# FPGA.net
KiCad netlist of a schematic drawn in Altium Designer
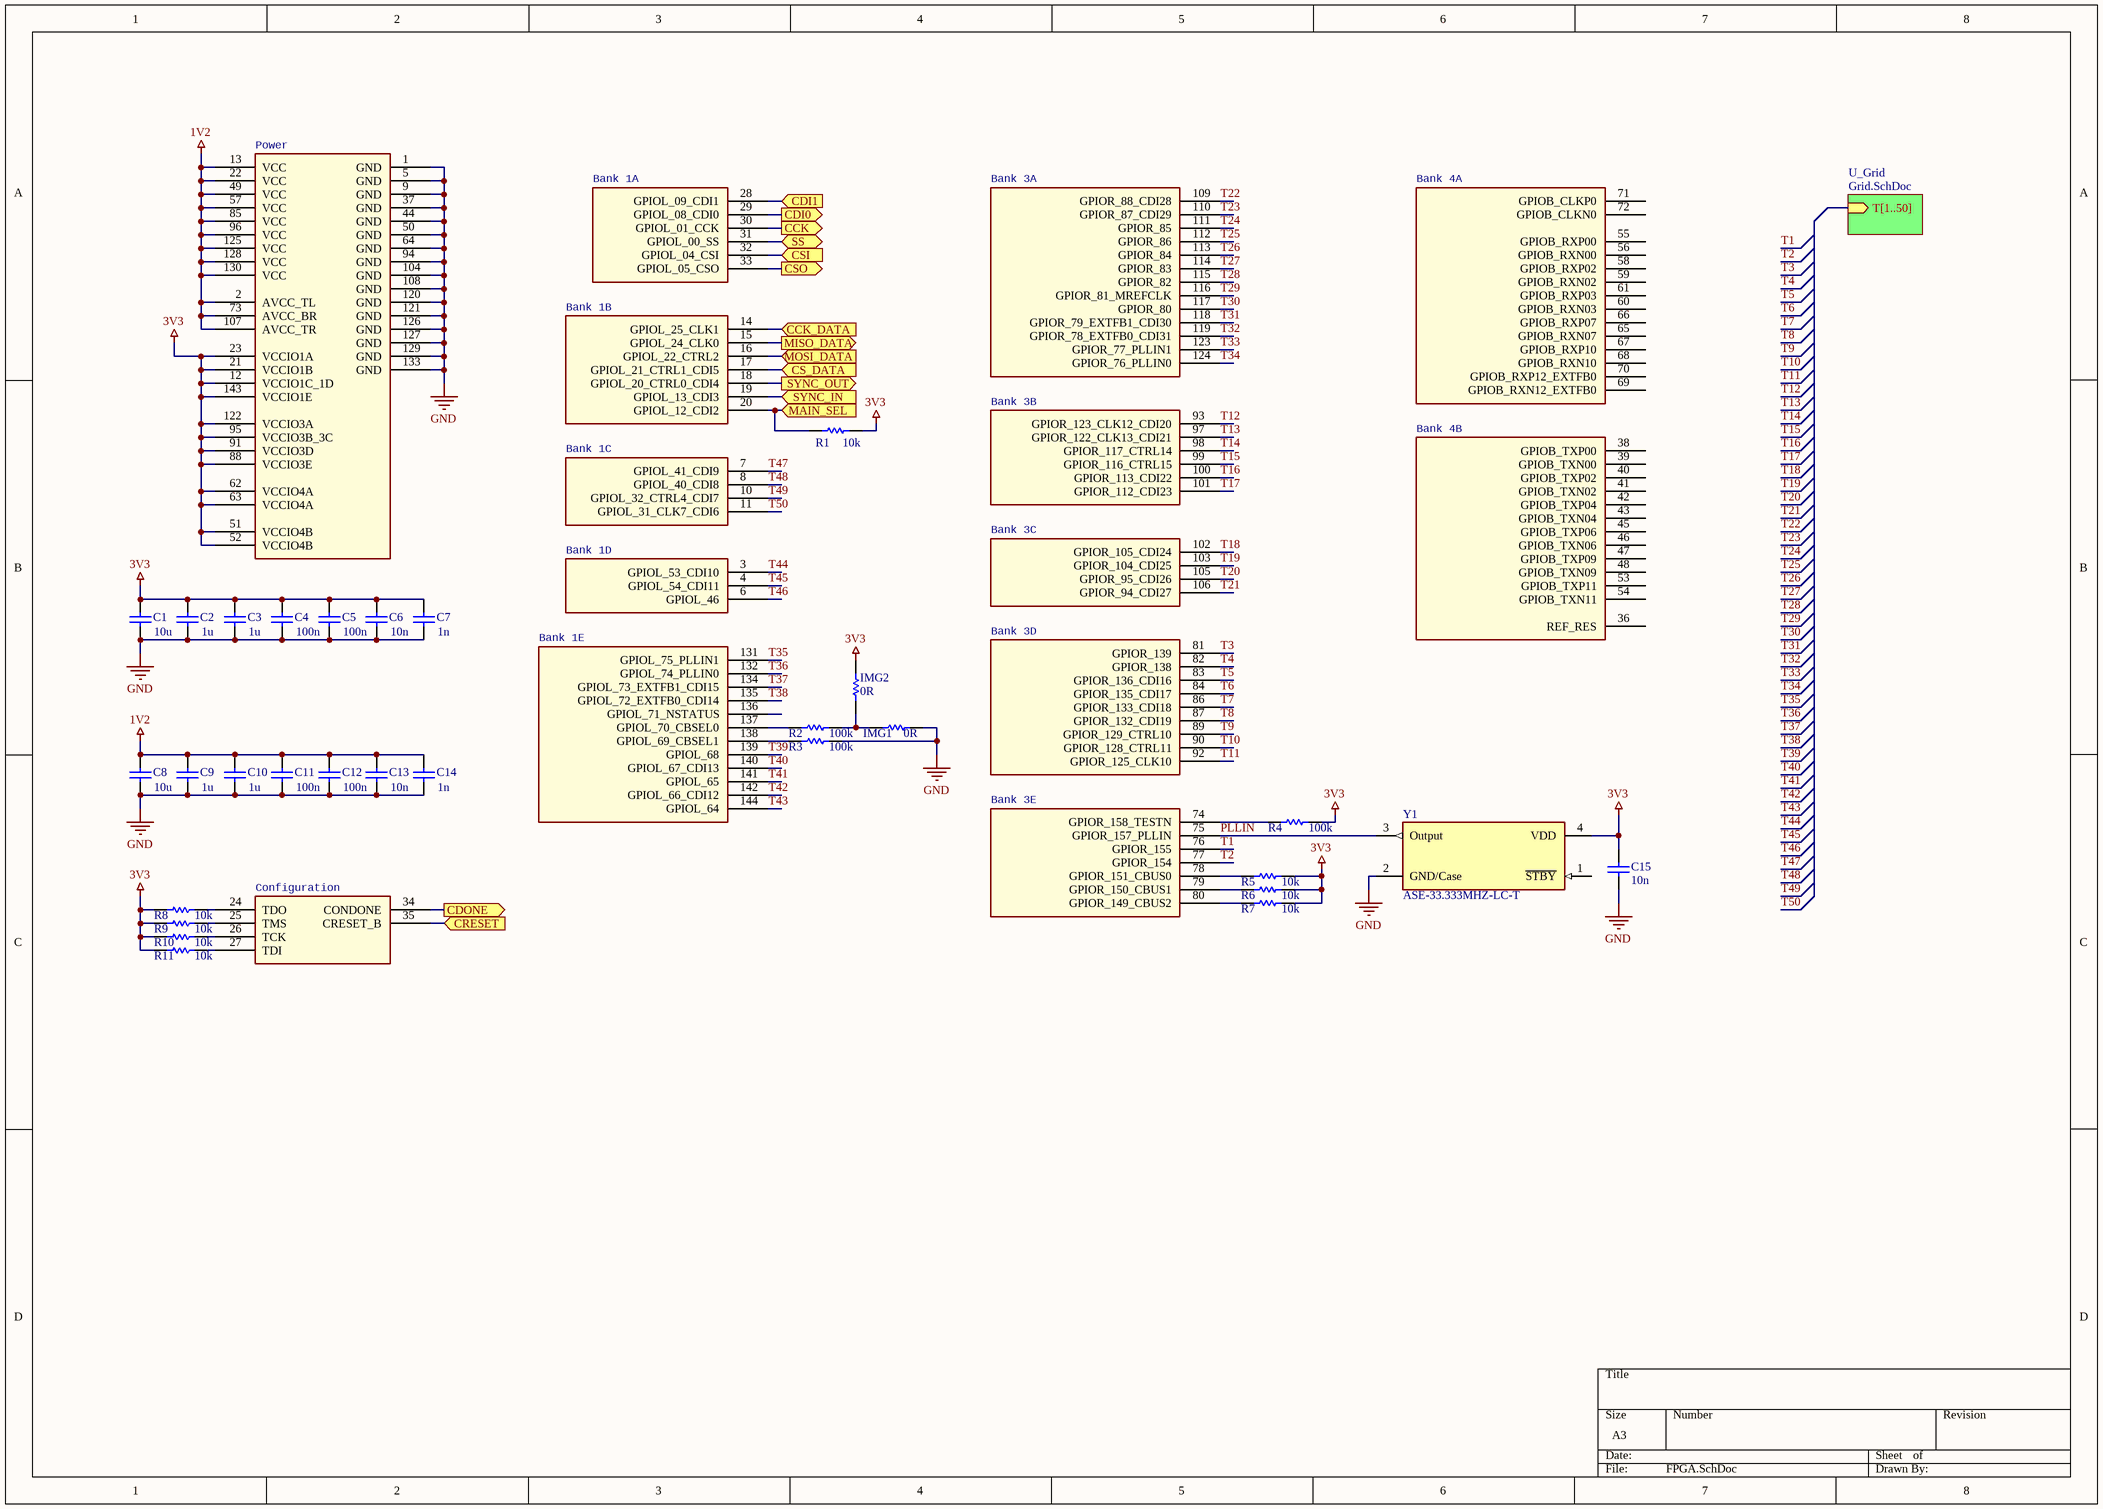
[diagram p0: FPGA.SchDoc]

(export (version "E")
  (design (tool "Eeschema 10.0.6"))
  (components
    (comp (ref "C1")
      (value "10u")
      (footprint "SAMS-C0603-2_M")
      (description "Multi-layer Ceramic Capacitor, -55 to 125 degC, 2-Pin SMD (0603), RoHS, Tape and Reel")
      (fields (field (name "MANUFACTURER") "Samsung Electro-Mechanics"))
      (libsource (lib "Altium Content Vault") (part "CAP-NP-2"))
    )
    (comp (ref "C2")
      (value "1u")
      (footprint "SAMS-C0603-2_M")
      (description "Multi-layer Ceramic Capacitor, -55 to 125 degC, 2-Pin SMD (0603), RoHS, Tape and Reel")
      (fields (field (name "MANUFACTURER") "Samsung Electro-Mechanics"))
      (libsource (lib "Altium Content Vault") (part "CAP-NP-2"))
    )
    (comp (ref "C3")
      (value "1u")
      (footprint "SAMS-C0603-2_M")
      (description "Multi-layer Ceramic Capacitor, -55 to 125 degC, 2-Pin SMD (0603), RoHS, Tape and Reel")
      (fields (field (name "MANUFACTURER") "Samsung Electro-Mechanics"))
      (libsource (lib "Altium Content Vault") (part "CAP-NP-2"))
    )
    (comp (ref "C4")
      (value "100n")
      (footprint "SAMS-C0603-2_M")
      (description "Multi-layer Ceramic Capacitor, -55 to 125 degC, 2-Pin SMD (0603), RoHS, Tape and Reel")
      (fields (field (name "MANUFACTURER") "Samsung Electro-Mechanics"))
      (libsource (lib "Altium Content Vault") (part "CAP-NP-2"))
    )
    (comp (ref "C5")
      (value "100n")
      (footprint "SAMS-C0603-2_M")
      (description "Multi-layer Ceramic Capacitor, -55 to 125 degC, 2-Pin SMD (0603), RoHS, Tape and Reel")
      (fields (field (name "MANUFACTURER") "Samsung Electro-Mechanics"))
      (libsource (lib "Altium Content Vault") (part "CAP-NP-2"))
    )
    (comp (ref "C6")
      (value "10n")
      (footprint "SAMS-C0603-2_M")
      (description "Multi-layer Ceramic Capacitor, -55 to 125 degC, 2-Pin SMD (0603), RoHS, Tape and Reel")
      (fields (field (name "MANUFACTURER") "Samsung Electro-Mechanics"))
      (libsource (lib "Altium Content Vault") (part "CAP-NP-2"))
    )
    (comp (ref "C7")
      (value "1n")
      (footprint "SAMS-C0603-2_M")
      (description "Multi-layer Ceramic Capacitor, -55 to 125 degC, 2-Pin SMD (0603), RoHS, Tape and Reel")
      (fields (field (name "MANUFACTURER") "Samsung Electro-Mechanics"))
      (libsource (lib "Altium Content Vault") (part "CAP-NP-2"))
    )
    (comp (ref "C8")
      (value "10u")
      (footprint "SAMS-C0603-2_M")
      (description "Multi-layer Ceramic Capacitor, -55 to 125 degC, 2-Pin SMD (0603), RoHS, Tape and Reel")
      (fields (field (name "MANUFACTURER") "Samsung Electro-Mechanics"))
      (libsource (lib "Altium Content Vault") (part "CAP-NP-2"))
    )
    (comp (ref "C9")
      (value "1u")
      (footprint "SAMS-C0603-2_M")
      (description "Multi-layer Ceramic Capacitor, -55 to 125 degC, 2-Pin SMD (0603), RoHS, Tape and Reel")
      (fields (field (name "MANUFACTURER") "Samsung Electro-Mechanics"))
      (libsource (lib "Altium Content Vault") (part "CAP-NP-2"))
    )
    (comp (ref "C10")
      (value "1u")
      (footprint "SAMS-C0603-2_M")
      (description "Multi-layer Ceramic Capacitor, -55 to 125 degC, 2-Pin SMD (0603), RoHS, Tape and Reel")
      (fields (field (name "MANUFACTURER") "Samsung Electro-Mechanics"))
      (libsource (lib "Altium Content Vault") (part "CAP-NP-2"))
    )
    (comp (ref "C11")
      (value "100n")
      (footprint "SAMS-C0603-2_M")
      (description "Multi-layer Ceramic Capacitor, -55 to 125 degC, 2-Pin SMD (0603), RoHS, Tape and Reel")
      (fields (field (name "MANUFACTURER") "Samsung Electro-Mechanics"))
      (libsource (lib "Altium Content Vault") (part "CAP-NP-2"))
    )
    (comp (ref "C12")
      (value "100n")
      (footprint "SAMS-C0603-2_M")
      (description "Multi-layer Ceramic Capacitor, -55 to 125 degC, 2-Pin SMD (0603), RoHS, Tape and Reel")
      (fields (field (name "MANUFACTURER") "Samsung Electro-Mechanics"))
      (libsource (lib "Altium Content Vault") (part "CAP-NP-2"))
    )
    (comp (ref "C13")
      (value "10n")
      (footprint "SAMS-C0603-2_M")
      (description "Multi-layer Ceramic Capacitor, -55 to 125 degC, 2-Pin SMD (0603), RoHS, Tape and Reel")
      (fields (field (name "MANUFACTURER") "Samsung Electro-Mechanics"))
      (libsource (lib "Altium Content Vault") (part "CAP-NP-2"))
    )
    (comp (ref "C14")
      (value "1n")
      (footprint "SAMS-C0603-2_M")
      (description "Multi-layer Ceramic Capacitor, -55 to 125 degC, 2-Pin SMD (0603), RoHS, Tape and Reel")
      (fields (field (name "MANUFACTURER") "Samsung Electro-Mechanics"))
      (libsource (lib "Altium Content Vault") (part "CAP-NP-2"))
    )
    (comp (ref "C15")
      (value "10n")
      (footprint "SAMS-C0603-2_M")
      (description "Multi-layer Ceramic Capacitor, -55 to 125 degC, 2-Pin SMD (0603), RoHS, Tape and Reel")
      (fields (field (name "MANUFACTURER") "Samsung Electro-Mechanics"))
      (libsource (lib "Altium Content Vault") (part "CAP-NP-2"))
    )
    (comp (ref "IMG1")
      (value "0R")
      (footprint "RESC1005X40X20NL05T10")
      (fields
        (field (name "MANUFACTURER") "Vishay BCcomponents")
        (field (name "PART NUMBER") "TNPW040210K0DEED")
      )
      (libsource (lib "Altium Content Vault") (part "RES"))
    )
    (comp (ref "IMG2")
      (value "0R")
      (footprint "RESC1005X40X20NL05T10")
      (fields
        (field (name "MANUFACTURER") "Vishay BCcomponents")
        (field (name "PART NUMBER") "TNPW040210K0DEED")
      )
      (libsource (lib "Altium Content Vault") (part "RES"))
    )
    (comp (ref "R1")
      (value "10k")
      (footprint "RESC1609X55X30LL15T15")
      (description "Chip Resistor, 10 KOhm, +/- 1%, 0.1 W, -55 to 155 degC, 0603 (1608 Metric), RoHS, Tape and Reel")
      (fields (field (name "TOLERANCE") "1%") (field (name "MANUFACTURER") "Panasonic"))
      (libsource (lib "Altium Content Vault") (part "RES-2"))
    )
    (comp (ref "R2")
      (value "100k")
      (footprint "RESC1609X55X30LL15T15")
      (description "Chip Resistor, 10 KOhm, +/- 1%, 0.1 W, -55 to 155 degC, 0603 (1608 Metric), RoHS, Tape and Reel")
      (fields (field (name "TOLERANCE") "1%") (field (name "MANUFACTURER") "Panasonic"))
      (libsource (lib "Altium Content Vault") (part "RES-2"))
    )
    (comp (ref "R3")
      (value "100k")
      (footprint "RESC1609X55X30LL15T15")
      (description "Chip Resistor, 10 KOhm, +/- 1%, 0.1 W, -55 to 155 degC, 0603 (1608 Metric), RoHS, Tape and Reel")
      (fields (field (name "TOLERANCE") "1%") (field (name "MANUFACTURER") "Panasonic"))
      (libsource (lib "Altium Content Vault") (part "RES-2"))
    )
    (comp (ref "R4")
      (value "100k")
      (footprint "RESC1609X55X30LL15T15")
      (description "Chip Resistor, 10 KOhm, +/- 1%, 0.1 W, -55 to 155 degC, 0603 (1608 Metric), RoHS, Tape and Reel")
      (fields (field (name "TOLERANCE") "1%") (field (name "MANUFACTURER") "Panasonic"))
      (libsource (lib "Altium Content Vault") (part "RES-2"))
    )
    (comp (ref "R5")
      (value "10k")
      (footprint "RESC1609X55X30LL15T15")
      (description "Chip Resistor, 10 KOhm, +/- 1%, 0.1 W, -55 to 155 degC, 0603 (1608 Metric), RoHS, Tape and Reel")
      (fields (field (name "TOLERANCE") "1%") (field (name "MANUFACTURER") "Panasonic"))
      (libsource (lib "Altium Content Vault") (part "RES-2"))
    )
    (comp (ref "R6")
      (value "10k")
      (footprint "RESC1609X55X30LL15T15")
      (description "Chip Resistor, 10 KOhm, +/- 1%, 0.1 W, -55 to 155 degC, 0603 (1608 Metric), RoHS, Tape and Reel")
      (fields (field (name "TOLERANCE") "1%") (field (name "MANUFACTURER") "Panasonic"))
      (libsource (lib "Altium Content Vault") (part "RES-2"))
    )
    (comp (ref "R7")
      (value "10k")
      (footprint "RESC1609X55X30LL15T15")
      (description "Chip Resistor, 10 KOhm, +/- 1%, 0.1 W, -55 to 155 degC, 0603 (1608 Metric), RoHS, Tape and Reel")
      (fields (field (name "TOLERANCE") "1%") (field (name "MANUFACTURER") "Panasonic"))
      (libsource (lib "Altium Content Vault") (part "RES-2"))
    )
    (comp (ref "R8")
      (value "10k")
      (footprint "RESC1609X55X30LL15T15")
      (description "Chip Resistor, 10 KOhm, +/- 1%, 0.1 W, -55 to 155 degC, 0603 (1608 Metric), RoHS, Tape and Reel")
      (fields (field (name "TOLERANCE") "1%") (field (name "MANUFACTURER") "Panasonic"))
      (libsource (lib "Altium Content Vault") (part "RES-2"))
    )
    (comp (ref "R9")
      (value "10k")
      (footprint "RESC1609X55X30LL15T15")
      (description "Chip Resistor, 10 KOhm, +/- 1%, 0.1 W, -55 to 155 degC, 0603 (1608 Metric), RoHS, Tape and Reel")
      (fields (field (name "TOLERANCE") "1%") (field (name "MANUFACTURER") "Panasonic"))
      (libsource (lib "Altium Content Vault") (part "RES-2"))
    )
    (comp (ref "R10")
      (value "10k")
      (footprint "RESC1609X55X30LL15T15")
      (description "Chip Resistor, 10 KOhm, +/- 1%, 0.1 W, -55 to 155 degC, 0603 (1608 Metric), RoHS, Tape and Reel")
      (fields (field (name "TOLERANCE") "1%") (field (name "MANUFACTURER") "Panasonic"))
      (libsource (lib "Altium Content Vault") (part "RES-2"))
    )
    (comp (ref "R11")
      (value "10k")
      (footprint "RESC1609X55X30LL15T15")
      (description "Chip Resistor, 10 KOhm, +/- 1%, 0.1 W, -55 to 155 degC, 0603 (1608 Metric), RoHS, Tape and Reel")
      (fields (field (name "TOLERANCE") "1%") (field (name "MANUFACTURER") "Panasonic"))
      (libsource (lib "Altium Content Vault") (part "RES-2"))
    )
    (comp (ref "U1")
      (value "T8Q144Cx")
      (footprint "LQFP144")
      (libsource (lib "Orcad Libraries") (part "T8Q144Cx"))
    )
    (comp (ref "Y1")
      (value "ASE-33.333MHZ-LC-T")
      (footprint "FP-ASE-MFG")
      (description "XTAL Oscillator 33.333MHz ±50ppm CMOS 3.3V 4-SMD 3.2mm x 2.5mm")
      (libsource (lib "Altium Content Vault") (part "61a724e6190563596ac712fef61ad37"))
    )
  )
  (nets
    (net (code "1") (name "/CCK") (class "Default")
      (node (ref "U1") (pin "30") (pinfunction "GPIOL_01_CCK_30") (pintype "passive"))
    )
    (net (code "2") (name "/CCK_DATA") (class "Default")
      (node (ref "U1") (pin "14") (pinfunction "GPIOL_25_CLK1_14") (pintype "passive"))
    )
    (net (code "3") (name "/CDI0") (class "Default")
      (node (ref "U1") (pin "29") (pinfunction "GPIOL_08_CDI0_29") (pintype "passive"))
    )
    (net (code "4") (name "/CDI1") (class "Default")
      (node (ref "U1") (pin "28") (pinfunction "GPIOL_09_CDI1_28") (pintype "passive"))
    )
    (net (code "5") (name "/CDONE") (class "Default")
      (node (ref "U1") (pin "34") (pinfunction "CONDONE_34") (pintype "passive"))
    )
    (net (code "6") (name "/CRESET") (class "Default")
      (node (ref "U1") (pin "35") (pinfunction "CRESET_B_35") (pintype "passive"))
    )
    (net (code "7") (name "/CSI") (class "Default")
      (node (ref "U1") (pin "32") (pinfunction "GPIOL_04_CSI_32") (pintype "passive"))
    )
    (net (code "8") (name "/CSO") (class "Default")
      (node (ref "U1") (pin "33") (pinfunction "GPIOL_05_CSO_33") (pintype "passive"))
    )
    (net (code "9") (name "/CS_DATA") (class "Default")
      (node (ref "U1") (pin "17") (pinfunction "GPIOL_21_CTRL1_CDI5_17") (pintype "passive"))
    )
    (net (code "10") (name "/MAIN_SEL") (class "Default")
      (node (ref "R1") (pin "2") (pinfunction "2_2") (pintype "passive"))
      (node (ref "U1") (pin "20") (pinfunction "GPIOL_12_CDI2_20") (pintype "passive"))
    )
    (net (code "11") (name "/MISO_DATA") (class "Default")
      (node (ref "U1") (pin "15") (pinfunction "GPIOL_24_CLK0_15") (pintype "passive"))
    )
    (net (code "12") (name "/MOSI_DATA") (class "Default")
      (node (ref "U1") (pin "16") (pinfunction "GPIOL_22_CTRL2_16") (pintype "passive"))
    )
    (net (code "13") (name "/PLLIN") (class "Default")
      (node (ref "U1") (pin "75") (pinfunction "GPIOR_157_PLLIN_75") (pintype "passive"))
      (node (ref "Y1") (pin "3") (pinfunction "Output_3") (pintype "output"))
    )
    (net (code "14") (name "/SS") (class "Default")
      (node (ref "U1") (pin "31") (pinfunction "GPIOL_00_SS_31") (pintype "passive"))
    )
    (net (code "15") (name "/SYNC_IN") (class "Default")
      (node (ref "U1") (pin "19") (pinfunction "GPIOL_13_CDI3_19") (pintype "passive"))
    )
    (net (code "16") (name "/SYNC_OUT") (class "Default")
      (node (ref "U1") (pin "18") (pinfunction "GPIOL_20_CTRL0_CDI4_18") (pintype "passive"))
    )
    (net (code "17") (name "/T1") (class "Default")
      (node (ref "U1") (pin "76") (pinfunction "GPIOR_155_76") (pintype "passive"))
    )
    (net (code "18") (name "/T2") (class "Default")
      (node (ref "U1") (pin "77") (pinfunction "GPIOR_154_77") (pintype "passive"))
    )
    (net (code "19") (name "/T3") (class "Default")
      (node (ref "U1") (pin "81") (pinfunction "GPIOR_139_81") (pintype "passive"))
    )
    (net (code "20") (name "/T4") (class "Default")
      (node (ref "U1") (pin "82") (pinfunction "GPIOR_138_82") (pintype "passive"))
    )
    (net (code "21") (name "/T5") (class "Default")
      (node (ref "U1") (pin "83") (pinfunction "GPIOR_136_CDI16_83") (pintype "passive"))
    )
    (net (code "22") (name "/T6") (class "Default")
      (node (ref "U1") (pin "84") (pinfunction "GPIOR_135_CDI17_84") (pintype "passive"))
    )
    (net (code "23") (name "/T7") (class "Default")
      (node (ref "U1") (pin "86") (pinfunction "GPIOR_133_CDI18_86") (pintype "passive"))
    )
    (net (code "24") (name "/T8") (class "Default")
      (node (ref "U1") (pin "87") (pinfunction "GPIOR_132_CDI19_87") (pintype "passive"))
    )
    (net (code "25") (name "/T9") (class "Default")
      (node (ref "U1") (pin "89") (pinfunction "GPIOR_129_CTRL10_89") (pintype "passive"))
    )
    (net (code "26") (name "/T10") (class "Default")
      (node (ref "U1") (pin "90") (pinfunction "GPIOR_128_CTRL11_90") (pintype "passive"))
    )
    (net (code "27") (name "/T11") (class "Default")
      (node (ref "U1") (pin "92") (pinfunction "GPIOR_125_CLK10_92") (pintype "passive"))
    )
    (net (code "28") (name "/T12") (class "Default")
      (node (ref "U1") (pin "93") (pinfunction "GPIOR_123_CLK12_CDI20_93") (pintype "passive"))
    )
    (net (code "29") (name "/T13") (class "Default")
      (node (ref "U1") (pin "97") (pinfunction "GPIOR_122_CLK13_CDI21_97") (pintype "passive"))
    )
    (net (code "30") (name "/T14") (class "Default")
      (node (ref "U1") (pin "98") (pinfunction "GPIOR_117_CTRL14_98") (pintype "passive"))
    )
    (net (code "31") (name "/T15") (class "Default")
      (node (ref "U1") (pin "99") (pinfunction "GPIOR_116_CTRL15_99") (pintype "passive"))
    )
    (net (code "32") (name "/T16") (class "Default")
      (node (ref "U1") (pin "100") (pinfunction "GPIOR_113_CDI22_100") (pintype "passive"))
    )
    (net (code "33") (name "/T17") (class "Default")
      (node (ref "U1") (pin "101") (pinfunction "GPIOR_112_CDI23_101") (pintype "passive"))
    )
    (net (code "34") (name "/T18") (class "Default")
      (node (ref "U1") (pin "102") (pinfunction "GPIOR_105_CDI24_102") (pintype "passive"))
    )
    (net (code "35") (name "/T19") (class "Default")
      (node (ref "U1") (pin "103") (pinfunction "GPIOR_104_CDI25_103") (pintype "passive"))
    )
    (net (code "36") (name "/T20") (class "Default")
      (node (ref "U1") (pin "105") (pinfunction "GPIOR_95_CDI26_105") (pintype "passive"))
    )
    (net (code "37") (name "/T21") (class "Default")
      (node (ref "U1") (pin "106") (pinfunction "GPIOR_94_CDI27_106") (pintype "passive"))
    )
    (net (code "38") (name "/T22") (class "Default")
      (node (ref "U1") (pin "109") (pinfunction "GPIOR_88_CDI28_109") (pintype "passive"))
    )
    (net (code "39") (name "/T23") (class "Default")
      (node (ref "U1") (pin "110") (pinfunction "GPIOR_87_CDI29_110") (pintype "passive"))
    )
    (net (code "40") (name "/T24") (class "Default")
      (node (ref "U1") (pin "111") (pinfunction "GPIOR_85_111") (pintype "passive"))
    )
    (net (code "41") (name "/T25") (class "Default")
      (node (ref "U1") (pin "112") (pinfunction "GPIOR_86_112") (pintype "passive"))
    )
    (net (code "42") (name "/T26") (class "Default")
      (node (ref "U1") (pin "113") (pinfunction "GPIOR_84_113") (pintype "passive"))
    )
    (net (code "43") (name "/T27") (class "Default")
      (node (ref "U1") (pin "114") (pinfunction "GPIOR_83_114") (pintype "passive"))
    )
    (net (code "44") (name "/T28") (class "Default")
      (node (ref "U1") (pin "115") (pinfunction "GPIOR_82_115") (pintype "passive"))
    )
    (net (code "45") (name "/T29") (class "Default")
      (node (ref "U1") (pin "116") (pinfunction "GPIOR_81_MREFCLK_116") (pintype "passive"))
    )
    (net (code "46") (name "/T30") (class "Default")
      (node (ref "U1") (pin "117") (pinfunction "GPIOR_80_117") (pintype "passive"))
    )
    (net (code "47") (name "/T31") (class "Default")
      (node (ref "U1") (pin "118") (pinfunction "GPIOR_79_EXTFB1_CDI30_118") (pintype "passive"))
    )
    (net (code "48") (name "/T32") (class "Default")
      (node (ref "U1") (pin "119") (pinfunction "GPIOR_78_EXTFB0_CDI31_119") (pintype "passive"))
    )
    (net (code "49") (name "/T33") (class "Default")
      (node (ref "U1") (pin "123") (pinfunction "GPIOR_77_PLLIN1_123") (pintype "passive"))
    )
    (net (code "50") (name "/T34") (class "Default")
      (node (ref "U1") (pin "124") (pinfunction "GPIOR_76_PLLIN0_124") (pintype "passive"))
    )
    (net (code "51") (name "/T35") (class "Default")
      (node (ref "U1") (pin "131") (pinfunction "GPIOL_75_PLLIN1_131") (pintype "passive"))
    )
    (net (code "52") (name "/T36") (class "Default")
      (node (ref "U1") (pin "132") (pinfunction "GPIOL_74_PLLIN0_132") (pintype "passive"))
    )
    (net (code "53") (name "/T37") (class "Default")
      (node (ref "U1") (pin "134") (pinfunction "GPIOL_73_EXTFB1_CDI15_134") (pintype "passive"))
    )
    (net (code "54") (name "/T38") (class "Default")
      (node (ref "U1") (pin "135") (pinfunction "GPIOL_72_EXTFB0_CDI14_135") (pintype "passive"))
    )
    (net (code "55") (name "/T39") (class "Default")
      (node (ref "U1") (pin "139") (pinfunction "GPIOL_68_139") (pintype "passive"))
    )
    (net (code "56") (name "/T40") (class "Default")
      (node (ref "U1") (pin "140") (pinfunction "GPIOL_67_CDI13_140") (pintype "passive"))
    )
    (net (code "57") (name "/T41") (class "Default")
      (node (ref "U1") (pin "141") (pinfunction "GPIOL_65_141") (pintype "passive"))
    )
    (net (code "58") (name "/T42") (class "Default")
      (node (ref "U1") (pin "142") (pinfunction "GPIOL_66_CDI12_142") (pintype "passive"))
    )
    (net (code "59") (name "/T43") (class "Default")
      (node (ref "U1") (pin "144") (pinfunction "GPIOL_64_144") (pintype "passive"))
    )
    (net (code "60") (name "/T44") (class "Default")
      (node (ref "U1") (pin "3") (pinfunction "GPIOL_53_CDI10_3") (pintype "passive"))
    )
    (net (code "61") (name "/T45") (class "Default")
      (node (ref "U1") (pin "4") (pinfunction "GPIOL_54_CDI11_4") (pintype "passive"))
    )
    (net (code "62") (name "/T46") (class "Default")
      (node (ref "U1") (pin "6") (pinfunction "GPIOL_46_6") (pintype "passive"))
    )
    (net (code "63") (name "/T47") (class "Default")
      (node (ref "U1") (pin "7") (pinfunction "GPIOL_41_CDI9_7") (pintype "passive"))
    )
    (net (code "64") (name "/T48") (class "Default")
      (node (ref "U1") (pin "8") (pinfunction "GPIOL_40_CDI8_8") (pintype "passive"))
    )
    (net (code "65") (name "/T49") (class "Default")
      (node (ref "U1") (pin "10") (pinfunction "GPIOL_32_CTRL4_CDI7_10") (pintype "passive"))
    )
    (net (code "66") (name "/T50") (class "Default")
      (node (ref "U1") (pin "11") (pinfunction "GPIOL_31_CLK7_CDI6_11") (pintype "passive"))
    )
    (net (code "68") (name "1V2") (class "Default")
      (node (ref "C10") (pin "1") (pinfunction "1_1") (pintype "passive"))
      (node (ref "C11") (pin "1") (pinfunction "1_1") (pintype "passive"))
      (node (ref "C12") (pin "1") (pinfunction "1_1") (pintype "passive"))
      (node (ref "C13") (pin "1") (pinfunction "1_1") (pintype "passive"))
      (node (ref "C14") (pin "1") (pinfunction "1_1") (pintype "passive"))
      (node (ref "C8") (pin "1") (pinfunction "1_1") (pintype "passive"))
      (node (ref "C9") (pin "1") (pinfunction "1_1") (pintype "passive"))
      (node (ref "U1") (pin "107") (pinfunction "AVCC_TR_107") (pintype "power_in"))
      (node (ref "U1") (pin "125") (pinfunction "VCC_125") (pintype "power_in"))
      (node (ref "U1") (pin "128") (pinfunction "VCC_128") (pintype "power_in"))
      (node (ref "U1") (pin "13") (pinfunction "VCC_13") (pintype "power_in"))
      (node (ref "U1") (pin "130") (pinfunction "VCC_130") (pintype "power_in"))
      (node (ref "U1") (pin "2") (pinfunction "AVCC_TL_2") (pintype "power_in"))
      (node (ref "U1") (pin "22") (pinfunction "VCC_22") (pintype "power_in"))
      (node (ref "U1") (pin "49") (pinfunction "VCC_49") (pintype "power_in"))
      (node (ref "U1") (pin "57") (pinfunction "VCC_57") (pintype "power_in"))
      (node (ref "U1") (pin "73") (pinfunction "AVCC_BR_73") (pintype "power_in"))
      (node (ref "U1") (pin "85") (pinfunction "VCC_85") (pintype "power_in"))
      (node (ref "U1") (pin "96") (pinfunction "VCC_96") (pintype "power_in"))
    )
    (net (code "69") (name "3V3") (class "Default")
      (node (ref "C1") (pin "1") (pinfunction "1_1") (pintype "passive"))
      (node (ref "C15") (pin "2") (pinfunction "2_2") (pintype "passive"))
      (node (ref "C2") (pin "1") (pinfunction "1_1") (pintype "passive"))
      (node (ref "C3") (pin "1") (pinfunction "1_1") (pintype "passive"))
      (node (ref "C4") (pin "1") (pinfunction "1_1") (pintype "passive"))
      (node (ref "C5") (pin "1") (pinfunction "1_1") (pintype "passive"))
      (node (ref "C6") (pin "1") (pinfunction "1_1") (pintype "passive"))
      (node (ref "C7") (pin "1") (pinfunction "1_1") (pintype "passive"))
      (node (ref "IMG2") (pin "2") (pinfunction "2_2") (pintype "passive"))
      (node (ref "R1") (pin "1") (pinfunction "1_1") (pintype "passive"))
      (node (ref "R10") (pin "1") (pinfunction "1_1") (pintype "passive"))
      (node (ref "R11") (pin "1") (pinfunction "1_1") (pintype "passive"))
      (node (ref "R4") (pin "2") (pinfunction "2_2") (pintype "passive"))
      (node (ref "R5") (pin "2") (pinfunction "2_2") (pintype "passive"))
      (node (ref "R6") (pin "2") (pinfunction "2_2") (pintype "passive"))
      (node (ref "R7") (pin "2") (pinfunction "2_2") (pintype "passive"))
      (node (ref "R8") (pin "1") (pinfunction "1_1") (pintype "passive"))
      (node (ref "R9") (pin "1") (pinfunction "1_1") (pintype "passive"))
      (node (ref "U1") (pin "12") (pinfunction "VCCIO1C_1D_12") (pintype "power_in"))
      (node (ref "U1") (pin "122") (pinfunction "VCCIO3A_122") (pintype "power_in"))
      (node (ref "U1") (pin "143") (pinfunction "VCCIO1E_143") (pintype "power_in"))
      (node (ref "U1") (pin "21") (pinfunction "VCCIO1B_21") (pintype "power_in"))
      (node (ref "U1") (pin "23") (pinfunction "VCCIO1A_23") (pintype "power_in"))
      (node (ref "U1") (pin "51") (pinfunction "VCCIO4B_51") (pintype "power_in"))
      (node (ref "U1") (pin "52") (pinfunction "VCCIO4B_52") (pintype "power_in"))
      (node (ref "U1") (pin "62") (pinfunction "VCCIO4A_62") (pintype "power_in"))
      (node (ref "U1") (pin "63") (pinfunction "VCCIO4A_63") (pintype "power_in"))
      (node (ref "U1") (pin "88") (pinfunction "VCCIO3E_88") (pintype "power_in"))
      (node (ref "U1") (pin "91") (pinfunction "VCCIO3D_91") (pintype "power_in"))
      (node (ref "U1") (pin "95") (pinfunction "VCCIO3B_3C_95") (pintype "power_in"))
      (node (ref "Y1") (pin "4") (pinfunction "VDD_4") (pintype "power_in"))
    )
    (net (code "70") (name "GND") (class "Default")
      (node (ref "C1") (pin "2") (pinfunction "2_2") (pintype "passive"))
      (node (ref "C10") (pin "2") (pinfunction "2_2") (pintype "passive"))
      (node (ref "C11") (pin "2") (pinfunction "2_2") (pintype "passive"))
      (node (ref "C12") (pin "2") (pinfunction "2_2") (pintype "passive"))
      (node (ref "C13") (pin "2") (pinfunction "2_2") (pintype "passive"))
      (node (ref "C14") (pin "2") (pinfunction "2_2") (pintype "passive"))
      (node (ref "C15") (pin "1") (pinfunction "1_1") (pintype "passive"))
      (node (ref "C2") (pin "2") (pinfunction "2_2") (pintype "passive"))
      (node (ref "C3") (pin "2") (pinfunction "2_2") (pintype "passive"))
      (node (ref "C4") (pin "2") (pinfunction "2_2") (pintype "passive"))
      (node (ref "C5") (pin "2") (pinfunction "2_2") (pintype "passive"))
      (node (ref "C6") (pin "2") (pinfunction "2_2") (pintype "passive"))
      (node (ref "C7") (pin "2") (pinfunction "2_2") (pintype "passive"))
      (node (ref "C8") (pin "2") (pinfunction "2_2") (pintype "passive"))
      (node (ref "C9") (pin "2") (pinfunction "2_2") (pintype "passive"))
      (node (ref "IMG1") (pin "2") (pinfunction "2_2") (pintype "passive"))
      (node (ref "R3") (pin "2") (pinfunction "2_2") (pintype "passive"))
      (node (ref "U1") (pin "1") (pinfunction "GND_1") (pintype "power_in"))
      (node (ref "U1") (pin "104") (pinfunction "GND_104") (pintype "power_in"))
      (node (ref "U1") (pin "108") (pinfunction "GND_108") (pintype "power_in"))
      (node (ref "U1") (pin "120") (pinfunction "GND_120") (pintype "power_in"))
      (node (ref "U1") (pin "121") (pinfunction "GND_121") (pintype "power_in"))
      (node (ref "U1") (pin "126") (pinfunction "GND_126") (pintype "power_in"))
      (node (ref "U1") (pin "127") (pinfunction "GND_127") (pintype "power_in"))
      (node (ref "U1") (pin "129") (pinfunction "GND_129") (pintype "power_in"))
      (node (ref "U1") (pin "133") (pinfunction "GND_133") (pintype "power_in"))
      (node (ref "U1") (pin "37") (pinfunction "GND_37") (pintype "power_in"))
      (node (ref "U1") (pin "44") (pinfunction "GND_44") (pintype "power_in"))
      (node (ref "U1") (pin "5") (pinfunction "GND_5") (pintype "power_in"))
      (node (ref "U1") (pin "50") (pinfunction "GND_50") (pintype "power_in"))
      (node (ref "U1") (pin "64") (pinfunction "GND_64") (pintype "power_in"))
      (node (ref "U1") (pin "9") (pinfunction "GND_9") (pintype "power_in"))
      (node (ref "U1") (pin "94") (pinfunction "GND_94") (pintype "power_in"))
      (node (ref "Y1") (pin "2") (pinfunction "GND/Case_2") (pintype "power_in"))
    )
    (net (code "71") (name "Net-(IMG1-Pad1)") (class "Default")
      (node (ref "IMG1") (pin "1") (pinfunction "1_1") (pintype "passive"))
      (node (ref "IMG2") (pin "1") (pinfunction "1_1") (pintype "passive"))
      (node (ref "R2") (pin "2") (pinfunction "2_2") (pintype "passive"))
    )
    (net (code "72") (name "Net-(U1B-TCK)") (class "Default")
      (node (ref "R10") (pin "2") (pinfunction "2_2") (pintype "passive"))
      (node (ref "U1") (pin "26") (pinfunction "TCK_26") (pintype "passive"))
    )
    (net (code "73") (name "Net-(U1B-TDI)") (class "Default")
      (node (ref "R11") (pin "2") (pinfunction "2_2") (pintype "passive"))
      (node (ref "U1") (pin "27") (pinfunction "TDI_27") (pintype "passive"))
    )
    (net (code "74") (name "Net-(U1B-TDO)") (class "Default")
      (node (ref "R8") (pin "2") (pinfunction "2_2") (pintype "passive"))
      (node (ref "U1") (pin "24") (pinfunction "TDO_24") (pintype "passive"))
    )
    (net (code "75") (name "Net-(U1B-TMS)") (class "Default")
      (node (ref "R9") (pin "2") (pinfunction "2_2") (pintype "passive"))
      (node (ref "U1") (pin "25") (pinfunction "TMS_25") (pintype "passive"))
    )
    (net (code "76") (name "Net-(U1G-GPIOL_69_CBSEL1)") (class "Default")
      (node (ref "R3") (pin "1") (pinfunction "1_1") (pintype "passive"))
      (node (ref "U1") (pin "138") (pinfunction "GPIOL_69_CBSEL1_138") (pintype "passive"))
    )
    (net (code "77") (name "Net-(U1G-GPIOL_70_CBSEL0)") (class "Default")
      (node (ref "R2") (pin "1") (pinfunction "1_1") (pintype "passive"))
      (node (ref "U1") (pin "137") (pinfunction "GPIOL_70_CBSEL0_137") (pintype "passive"))
    )
    (net (code "78") (name "Net-(U1L-GPIOR_149_CBUS2)") (class "Default")
      (node (ref "R7") (pin "1") (pinfunction "1_1") (pintype "passive"))
      (node (ref "U1") (pin "80") (pinfunction "GPIOR_149_CBUS2_80") (pintype "passive"))
    )
    (net (code "79") (name "Net-(U1L-GPIOR_150_CBUS1)") (class "Default")
      (node (ref "R6") (pin "1") (pinfunction "1_1") (pintype "passive"))
      (node (ref "U1") (pin "79") (pinfunction "GPIOR_150_CBUS1_79") (pintype "passive"))
    )
    (net (code "80") (name "Net-(U1L-GPIOR_151_CBUS0)") (class "Default")
      (node (ref "R5") (pin "1") (pinfunction "1_1") (pintype "passive"))
      (node (ref "U1") (pin "78") (pinfunction "GPIOR_151_CBUS0_78") (pintype "passive"))
    )
    (net (code "81") (name "Net-(U1L-GPIOR_158_TESTN)") (class "Default")
      (node (ref "R4") (pin "1") (pinfunction "1_1") (pintype "passive"))
      (node (ref "U1") (pin "74") (pinfunction "GPIOR_158_TESTN_74") (pintype "passive"))
    )
    (net (code "82") (name "unconnected-(U1G-GPIOL_71_NSTATUS-Pad136)") (class "Default")
      (node (ref "U1") (pin "136") (pinfunction "GPIOL_71_NSTATUS_136") (pintype "passive"))
    )
    (net (code "83") (name "unconnected-(U1M-GPIOB_CLKN0-Pad72)") (class "Default")
      (node (ref "U1") (pin "72") (pinfunction "GPIOB_CLKN0_72") (pintype "passive"))
    )
    (net (code "84") (name "unconnected-(U1M-GPIOB_CLKP0-Pad71)") (class "Default")
      (node (ref "U1") (pin "71") (pinfunction "GPIOB_CLKP0_71") (pintype "passive"))
    )
    (net (code "85") (name "unconnected-(U1M-GPIOB_RXN00-Pad56)") (class "Default")
      (node (ref "U1") (pin "56") (pinfunction "GPIOB_RXN00_56") (pintype "passive"))
    )
    (net (code "86") (name "unconnected-(U1M-GPIOB_RXN02-Pad59)") (class "Default")
      (node (ref "U1") (pin "59") (pinfunction "GPIOB_RXN02_59") (pintype "passive"))
    )
    (net (code "87") (name "unconnected-(U1M-GPIOB_RXN03-Pad60)") (class "Default")
      (node (ref "U1") (pin "60") (pinfunction "GPIOB_RXN03_60") (pintype "passive"))
    )
    (net (code "88") (name "unconnected-(U1M-GPIOB_RXN07-Pad65)") (class "Default")
      (node (ref "U1") (pin "65") (pinfunction "GPIOB_RXN07_65") (pintype "passive"))
    )
    (net (code "89") (name "unconnected-(U1M-GPIOB_RXN10-Pad68)") (class "Default")
      (node (ref "U1") (pin "68") (pinfunction "GPIOB_RXN10_68") (pintype "passive"))
    )
    (net (code "90") (name "unconnected-(U1M-GPIOB_RXN12_EXTFB0-Pad69)") (class "Default")
      (node (ref "U1") (pin "69") (pinfunction "GPIOB_RXN12_EXTFB0_69") (pintype "passive"))
    )
    (net (code "91") (name "unconnected-(U1M-GPIOB_RXP00-Pad55)") (class "Default")
      (node (ref "U1") (pin "55") (pinfunction "GPIOB_RXP00_55") (pintype "passive"))
    )
    (net (code "92") (name "unconnected-(U1M-GPIOB_RXP02-Pad58)") (class "Default")
      (node (ref "U1") (pin "58") (pinfunction "GPIOB_RXP02_58") (pintype "passive"))
    )
    (net (code "93") (name "unconnected-(U1M-GPIOB_RXP03-Pad61)") (class "Default")
      (node (ref "U1") (pin "61") (pinfunction "GPIOB_RXP03_61") (pintype "passive"))
    )
    (net (code "94") (name "unconnected-(U1M-GPIOB_RXP07-Pad66)") (class "Default")
      (node (ref "U1") (pin "66") (pinfunction "GPIOB_RXP07_66") (pintype "passive"))
    )
    (net (code "95") (name "unconnected-(U1M-GPIOB_RXP10-Pad67)") (class "Default")
      (node (ref "U1") (pin "67") (pinfunction "GPIOB_RXP10_67") (pintype "passive"))
    )
    (net (code "96") (name "unconnected-(U1M-GPIOB_RXP12_EXTFB0-Pad70)") (class "Default")
      (node (ref "U1") (pin "70") (pinfunction "GPIOB_RXP12_EXTFB0_70") (pintype "passive"))
    )
    (net (code "97") (name "unconnected-(U1N-GPIOB_TXN00-Pad39)") (class "Default")
      (node (ref "U1") (pin "39") (pinfunction "GPIOB_TXN00_39") (pintype "passive"))
    )
    (net (code "98") (name "unconnected-(U1N-GPIOB_TXN02-Pad41)") (class "Default")
      (node (ref "U1") (pin "41") (pinfunction "GPIOB_TXN02_41") (pintype "passive"))
    )
    (net (code "99") (name "unconnected-(U1N-GPIOB_TXN04-Pad43)") (class "Default")
      (node (ref "U1") (pin "43") (pinfunction "GPIOB_TXN04_43") (pintype "passive"))
    )
    (net (code "100") (name "unconnected-(U1N-GPIOB_TXN06-Pad46)") (class "Default")
      (node (ref "U1") (pin "46") (pinfunction "GPIOB_TXN06_46") (pintype "passive"))
    )
    (net (code "101") (name "unconnected-(U1N-GPIOB_TXN09-Pad48)") (class "Default")
      (node (ref "U1") (pin "48") (pinfunction "GPIOB_TXN09_48") (pintype "passive"))
    )
    (net (code "102") (name "unconnected-(U1N-GPIOB_TXN11-Pad54)") (class "Default")
      (node (ref "U1") (pin "54") (pinfunction "GPIOB_TXN11_54") (pintype "passive"))
    )
    (net (code "103") (name "unconnected-(U1N-GPIOB_TXP00-Pad38)") (class "Default")
      (node (ref "U1") (pin "38") (pinfunction "GPIOB_TXP00_38") (pintype "passive"))
    )
    (net (code "104") (name "unconnected-(U1N-GPIOB_TXP02-Pad40)") (class "Default")
      (node (ref "U1") (pin "40") (pinfunction "GPIOB_TXP02_40") (pintype "passive"))
    )
    (net (code "105") (name "unconnected-(U1N-GPIOB_TXP04-Pad42)") (class "Default")
      (node (ref "U1") (pin "42") (pinfunction "GPIOB_TXP04_42") (pintype "passive"))
    )
    (net (code "106") (name "unconnected-(U1N-GPIOB_TXP06-Pad45)") (class "Default")
      (node (ref "U1") (pin "45") (pinfunction "GPIOB_TXP06_45") (pintype "passive"))
    )
    (net (code "107") (name "unconnected-(U1N-GPIOB_TXP09-Pad47)") (class "Default")
      (node (ref "U1") (pin "47") (pinfunction "GPIOB_TXP09_47") (pintype "passive"))
    )
    (net (code "108") (name "unconnected-(U1N-GPIOB_TXP11-Pad53)") (class "Default")
      (node (ref "U1") (pin "53") (pinfunction "GPIOB_TXP11_53") (pintype "passive"))
    )
    (net (code "109") (name "unconnected-(U1N-REF_RES-Pad36)") (class "Default")
      (node (ref "U1") (pin "36") (pinfunction "REF_RES_36") (pintype "passive"))
    )
    (net (code "110") (name "unconnected-(Y1-~{STBY}-Pad1)") (class "Default")
      (node (ref "Y1") (pin "1") (pinfunction "~{STBY}_1") (pintype "input"))
    )
  )
)
